# power.net
KiCad netlist of a schematic drawn in Altium Designer
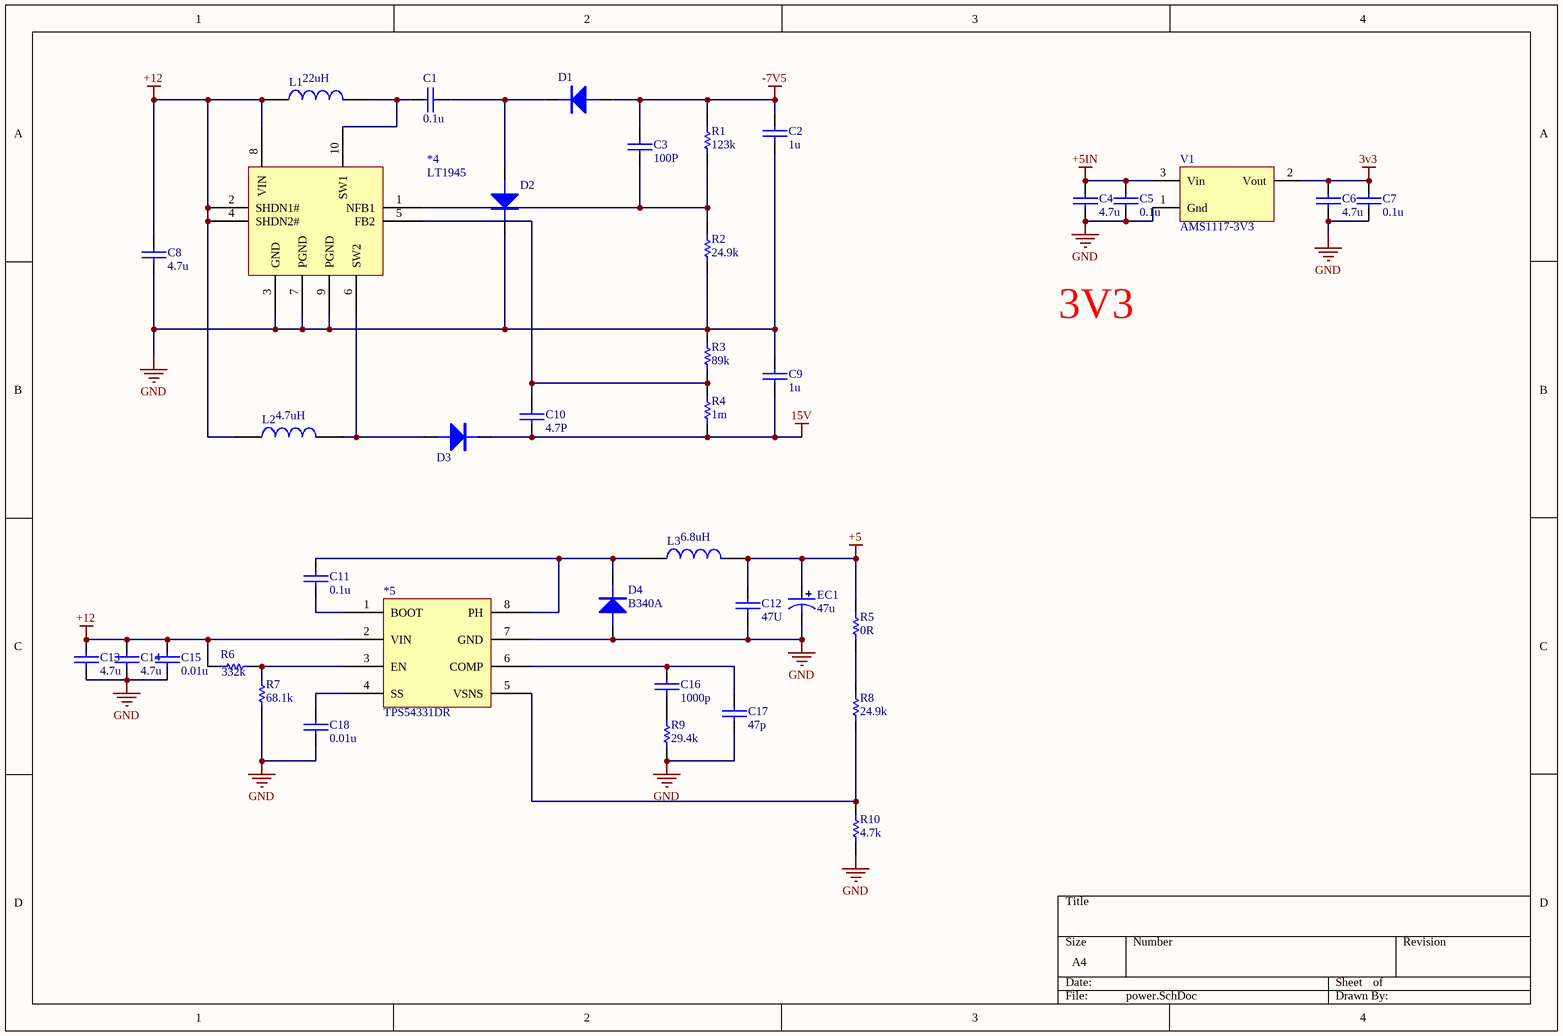
[diagram p0: power.SchDoc]

(export (version "E")
  (design (tool "Eeschema 10.0.6"))
  (components
    (comp (ref "*4")
      (value "LT1945")
      (footprint "LT1945EMS")
      (description "双通道升降压DCDC")
      (libsource (lib "0.03电源") (part "LT1945"))
    )
    (comp (ref "*5")
      (value "TPS54331DR")
      (footprint "SOIC-8")
      (description "降压型DC-DC")
      (libsource (lib "0.03电源") (part "TPS54331DR"))
    )
    (comp (ref "C1")
      (value "0.1u")
      (footprint "0603C")
      (description "无极性电容")
      (libsource (lib "1.00-阻容感") (part "CAP"))
    )
    (comp (ref "C2")
      (value "1u")
      (footprint "0603C")
      (description "无极性电容")
      (libsource (lib "1.00-阻容感") (part "CAP"))
    )
    (comp (ref "C3")
      (value "100P")
      (footprint "0603C")
      (description "无极性电容")
      (libsource (lib "1.00-阻容感") (part "CAP"))
    )
    (comp (ref "C4")
      (value "4.7u")
      (footprint "0603C")
      (description "无极性电容")
      (libsource (lib "1.00-阻容感") (part "CAP"))
    )
    (comp (ref "C5")
      (value "0.1u")
      (footprint "0603C")
      (description "无极性电容")
      (libsource (lib "1.00-阻容感") (part "CAP"))
    )
    (comp (ref "C6")
      (value "4.7u")
      (footprint "0603C")
      (description "无极性电容")
      (libsource (lib "1.00-阻容感") (part "CAP"))
    )
    (comp (ref "C7")
      (value "0.1u")
      (footprint "0603C")
      (description "无极性电容")
      (libsource (lib "1.00-阻容感") (part "CAP"))
    )
    (comp (ref "C8")
      (value "4.7u")
      (footprint "0603C")
      (description "无极性电容")
      (libsource (lib "1.00-阻容感") (part "CAP"))
    )
    (comp (ref "C9")
      (value "1u")
      (footprint "0603C")
      (description "无极性电容")
      (libsource (lib "1.00-阻容感") (part "CAP"))
    )
    (comp (ref "C10")
      (value "4.7P")
      (footprint "0603C")
      (description "无极性电容")
      (libsource (lib "1.00-阻容感") (part "CAP"))
    )
    (comp (ref "C11")
      (value "0.1u")
      (footprint "0603C")
      (description "无极性电容")
      (libsource (lib "1.00-阻容感") (part "CAP"))
    )
    (comp (ref "C12")
      (value "47U")
      (footprint "0603C")
      (description "无极性电容")
      (libsource (lib "1.00-阻容感") (part "CAP"))
    )
    (comp (ref "C13")
      (value "4.7u")
      (footprint "0603C")
      (description "无极性电容")
      (libsource (lib "1.00-阻容感") (part "CAP"))
    )
    (comp (ref "C14")
      (value "4.7u")
      (footprint "0603C")
      (description "无极性电容")
      (libsource (lib "1.00-阻容感") (part "CAP"))
    )
    (comp (ref "C15")
      (value "0.01u")
      (footprint "0603C")
      (description "无极性电容")
      (libsource (lib "1.00-阻容感") (part "CAP"))
    )
    (comp (ref "C16")
      (value "1000p")
      (footprint "0603C")
      (description "无极性电容")
      (libsource (lib "1.00-阻容感") (part "CAP"))
    )
    (comp (ref "C17")
      (value "47p")
      (footprint "0603C")
      (description "无极性电容")
      (libsource (lib "1.00-阻容感") (part "CAP"))
    )
    (comp (ref "C18")
      (value "0.01u")
      (footprint "0603C")
      (description "无极性电容")
      (libsource (lib "1.00-阻容感") (part "CAP"))
    )
    (comp (ref "D1")
      (value "B340A")
      (footprint "SMA/DO-214AC")
      (description "普通二极管")
      (libsource (lib "2.00-二极管") (part "DIODE"))
    )
    (comp (ref "D2")
      (value "B340A")
      (footprint "SMA/DO-214AC")
      (description "普通二极管")
      (libsource (lib "2.00-二极管") (part "DIODE"))
    )
    (comp (ref "D3")
      (value "B340A")
      (footprint "SMA/DO-214AC")
      (description "普通二极管")
      (libsource (lib "2.00-二极管") (part "DIODE"))
    )
    (comp (ref "D4")
      (value "B340A")
      (footprint "SMA/DO-214AC")
      (description "普通二极管")
      (libsource (lib "2.00-二极管") (part "DIODE"))
    )
    (comp (ref "EC1")
      (value "47u")
      (footprint "SMD-EC6.3X6.3X10")
      (description "贴片电解电容")
      (libsource (lib "1.00-阻容感") (part "ECAP"))
    )
    (comp (ref "L1")
      (value "22uH")
      (footprint "L-SMD-0630")
      (description "INDUCTOR")
      (libsource (lib "1.00-阻容感") (part "L"))
    )
    (comp (ref "L2")
      (value "4.7uH")
      (footprint "L-SMD-0630")
      (description "INDUCTOR")
      (libsource (lib "1.00-阻容感") (part "L"))
    )
    (comp (ref "L3")
      (value "6.8uH")
      (footprint "L-SMD-0630")
      (description "INDUCTOR")
      (libsource (lib "1.00-阻容感") (part "L"))
    )
    (comp (ref "R1")
      (value "123k")
      (footprint "0603R")
      (description "电阻")
      (libsource (lib "1.00-阻容感") (part "RES"))
    )
    (comp (ref "R2")
      (value "24.9k")
      (footprint "0603R")
      (description "电阻")
      (libsource (lib "1.00-阻容感") (part "RES"))
    )
    (comp (ref "R3")
      (value "89k")
      (footprint "0603R")
      (description "电阻")
      (libsource (lib "1.00-阻容感") (part "RES"))
    )
    (comp (ref "R4")
      (value "1m")
      (footprint "0603R")
      (description "电阻")
      (libsource (lib "1.00-阻容感") (part "RES"))
    )
    (comp (ref "R5")
      (value "0R")
      (footprint "0603R")
      (description "电阻")
      (libsource (lib "1.00-阻容感") (part "RES"))
    )
    (comp (ref "R6")
      (value "332k")
      (footprint "0603R")
      (description "电阻")
      (libsource (lib "1.00-阻容感") (part "RES"))
    )
    (comp (ref "R7")
      (value "68.1k")
      (footprint "0603R")
      (description "电阻")
      (libsource (lib "1.00-阻容感") (part "RES"))
    )
    (comp (ref "R8")
      (value "24.9k")
      (footprint "0603R")
      (description "电阻")
      (libsource (lib "1.00-阻容感") (part "RES"))
    )
    (comp (ref "R9")
      (value "29.4k")
      (footprint "0603R")
      (description "电阻")
      (libsource (lib "1.00-阻容感") (part "RES"))
    )
    (comp (ref "R10")
      (value "4.7k")
      (footprint "0603R")
      (description "电阻")
      (libsource (lib "1.00-阻容感") (part "RES"))
    )
    (comp (ref "V1")
      (value "AMS1117-3V3")
      (footprint "SOT223_L")
      (description "LDO")
      (libsource (lib "0.03电源") (part "AMS1117"))
    )
  )
  (nets
    (net (code "1") (name "+5") (class "Default")
      (node (ref "C12") (pin "2") (pinfunction "2_2") (pintype "passive"))
      (node (ref "EC1") (pin "1") (pinfunction "1_1") (pintype "passive"))
      (node (ref "L3") (pin "2") (pinfunction "2_2") (pintype "passive"))
      (node (ref "R5") (pin "2") (pinfunction "2_2") (pintype "passive"))
    )
    (net (code "2") (name "+5IN") (class "Default")
      (node (ref "C4") (pin "2") (pinfunction "2_2") (pintype "passive"))
      (node (ref "C5") (pin "2") (pinfunction "2_2") (pintype "passive"))
      (node (ref "V1") (pin "3") (pinfunction "Vin_3") (pintype "passive"))
    )
    (net (code "3") (name "+12") (class "Default")
      (node (ref "*4") (pin "2") (pinfunction "SHDN1#_2") (pintype "passive"))
      (node (ref "*4") (pin "4") (pinfunction "SHDN2#_4") (pintype "passive"))
      (node (ref "*4") (pin "8") (pinfunction "VIN_8") (pintype "passive"))
      (node (ref "*5") (pin "2") (pinfunction "VIN_2") (pintype "passive"))
      (node (ref "C13") (pin "2") (pinfunction "2_2") (pintype "passive"))
      (node (ref "C14") (pin "2") (pinfunction "2_2") (pintype "passive"))
      (node (ref "C15") (pin "2") (pinfunction "2_2") (pintype "passive"))
      (node (ref "C8") (pin "1") (pinfunction "1_1") (pintype "passive"))
      (node (ref "L1") (pin "1") (pinfunction "1_1") (pintype "passive"))
      (node (ref "L2") (pin "1") (pinfunction "1_1") (pintype "passive"))
      (node (ref "R6") (pin "2") (pinfunction "2_2") (pintype "passive"))
    )
    (net (code "4") (name "-7V5") (class "Default")
      (node (ref "C2") (pin "1") (pinfunction "1_1") (pintype "passive"))
      (node (ref "C3") (pin "1") (pinfunction "1_1") (pintype "passive"))
      (node (ref "D1") (pin "A") (pinfunction "A_A") (pintype "passive"))
      (node (ref "R1") (pin "2") (pinfunction "2_2") (pintype "passive"))
    )
    (net (code "5") (name "3v3") (class "Default")
      (node (ref "C6") (pin "2") (pinfunction "2_2") (pintype "passive"))
      (node (ref "C7") (pin "2") (pinfunction "2_2") (pintype "passive"))
      (node (ref "V1") (pin "2") (pinfunction "Vout_2") (pintype "passive"))
    )
    (net (code "6") (name "15V") (class "Default")
      (node (ref "C10") (pin "2") (pinfunction "2_2") (pintype "passive"))
      (node (ref "C9") (pin "2") (pinfunction "2_2") (pintype "passive"))
      (node (ref "D3") (pin "K") (pinfunction "K_K") (pintype "passive"))
      (node (ref "R4") (pin "2") (pinfunction "2_2") (pintype "passive"))
    )
    (net (code "7") (name "GND") (class "Default")
      (node (ref "*4") (pin "3") (pinfunction "GND_3") (pintype "passive"))
      (node (ref "*4") (pin "7") (pinfunction "PGND_7") (pintype "passive"))
      (node (ref "*4") (pin "9") (pinfunction "PGND_9") (pintype "passive"))
      (node (ref "*5") (pin "7") (pinfunction "GND_7") (pintype "passive"))
      (node (ref "C12") (pin "1") (pinfunction "1_1") (pintype "passive"))
      (node (ref "C13") (pin "1") (pinfunction "1_1") (pintype "passive"))
      (node (ref "C14") (pin "1") (pinfunction "1_1") (pintype "passive"))
      (node (ref "C15") (pin "1") (pinfunction "1_1") (pintype "passive"))
      (node (ref "C17") (pin "1") (pinfunction "1_1") (pintype "passive"))
      (node (ref "C18") (pin "1") (pinfunction "1_1") (pintype "passive"))
      (node (ref "C2") (pin "2") (pinfunction "2_2") (pintype "passive"))
      (node (ref "C4") (pin "1") (pinfunction "1_1") (pintype "passive"))
      (node (ref "C5") (pin "1") (pinfunction "1_1") (pintype "passive"))
      (node (ref "C6") (pin "1") (pinfunction "1_1") (pintype "passive"))
      (node (ref "C7") (pin "1") (pinfunction "1_1") (pintype "passive"))
      (node (ref "C8") (pin "2") (pinfunction "2_2") (pintype "passive"))
      (node (ref "C9") (pin "1") (pinfunction "1_1") (pintype "passive"))
      (node (ref "D2") (pin "K") (pinfunction "K_K") (pintype "passive"))
      (node (ref "D4") (pin "A") (pinfunction "A_A") (pintype "passive"))
      (node (ref "EC1") (pin "2") (pinfunction "2_2") (pintype "passive"))
      (node (ref "R10") (pin "1") (pinfunction "1_1") (pintype "passive"))
      (node (ref "R2") (pin "1") (pinfunction "1_1") (pintype "passive"))
      (node (ref "R3") (pin "2") (pinfunction "2_2") (pintype "passive"))
      (node (ref "R7") (pin "1") (pinfunction "1_1") (pintype "passive"))
      (node (ref "R9") (pin "1") (pinfunction "1_1") (pintype "passive"))
      (node (ref "V1") (pin "1") (pinfunction "Gnd_1") (pintype "passive"))
    )
    (net (code "8") (name "Net-(*4-FB2)") (class "Default")
      (node (ref "*4") (pin "5") (pinfunction "FB2_5") (pintype "passive"))
      (node (ref "C10") (pin "1") (pinfunction "1_1") (pintype "passive"))
      (node (ref "R3") (pin "1") (pinfunction "1_1") (pintype "passive"))
      (node (ref "R4") (pin "1") (pinfunction "1_1") (pintype "passive"))
    )
    (net (code "9") (name "Net-(*4-NFB1)") (class "Default")
      (node (ref "*4") (pin "1") (pinfunction "NFB1_1") (pintype "passive"))
      (node (ref "C3") (pin "2") (pinfunction "2_2") (pintype "passive"))
      (node (ref "R1") (pin "1") (pinfunction "1_1") (pintype "passive"))
      (node (ref "R2") (pin "2") (pinfunction "2_2") (pintype "passive"))
    )
    (net (code "10") (name "Net-(*4-SW1)") (class "Default")
      (node (ref "*4") (pin "10") (pinfunction "SW1_10") (pintype "passive"))
      (node (ref "C1") (pin "1") (pinfunction "1_1") (pintype "passive"))
      (node (ref "L1") (pin "2") (pinfunction "2_2") (pintype "passive"))
    )
    (net (code "11") (name "Net-(*4-SW2)") (class "Default")
      (node (ref "*4") (pin "6") (pinfunction "SW2_6") (pintype "passive"))
      (node (ref "D3") (pin "A") (pinfunction "A_A") (pintype "passive"))
      (node (ref "L2") (pin "2") (pinfunction "2_2") (pintype "passive"))
    )
    (net (code "12") (name "Net-(*5-BOOT)") (class "Default")
      (node (ref "*5") (pin "1") (pinfunction "BOOT_1") (pintype "passive"))
      (node (ref "C11") (pin "1") (pinfunction "1_1") (pintype "passive"))
    )
    (net (code "13") (name "Net-(*5-COMP)") (class "Default")
      (node (ref "*5") (pin "6") (pinfunction "COMP_6") (pintype "passive"))
      (node (ref "C16") (pin "2") (pinfunction "2_2") (pintype "passive"))
      (node (ref "C17") (pin "2") (pinfunction "2_2") (pintype "passive"))
    )
    (net (code "14") (name "Net-(*5-EN)") (class "Default")
      (node (ref "*5") (pin "3") (pinfunction "EN_3") (pintype "passive"))
      (node (ref "R6") (pin "1") (pinfunction "1_1") (pintype "passive"))
      (node (ref "R7") (pin "2") (pinfunction "2_2") (pintype "passive"))
    )
    (net (code "15") (name "Net-(*5-PH)") (class "Default")
      (node (ref "*5") (pin "8") (pinfunction "PH_8") (pintype "passive"))
      (node (ref "C11") (pin "2") (pinfunction "2_2") (pintype "passive"))
      (node (ref "D4") (pin "K") (pinfunction "K_K") (pintype "passive"))
      (node (ref "L3") (pin "1") (pinfunction "1_1") (pintype "passive"))
    )
    (net (code "16") (name "Net-(*5-SS)") (class "Default")
      (node (ref "*5") (pin "4") (pinfunction "SS_4") (pintype "passive"))
      (node (ref "C18") (pin "2") (pinfunction "2_2") (pintype "passive"))
    )
    (net (code "17") (name "Net-(*5-VSNS)") (class "Default")
      (node (ref "*5") (pin "5") (pinfunction "VSNS_5") (pintype "passive"))
      (node (ref "R10") (pin "2") (pinfunction "2_2") (pintype "passive"))
      (node (ref "R8") (pin "1") (pinfunction "1_1") (pintype "passive"))
    )
    (net (code "18") (name "Net-(C1-Pad2)") (class "Default")
      (node (ref "C1") (pin "2") (pinfunction "2_2") (pintype "passive"))
      (node (ref "D1") (pin "K") (pinfunction "K_K") (pintype "passive"))
      (node (ref "D2") (pin "A") (pinfunction "A_A") (pintype "passive"))
    )
    (net (code "19") (name "Net-(C16-Pad1)") (class "Default")
      (node (ref "C16") (pin "1") (pinfunction "1_1") (pintype "passive"))
      (node (ref "R9") (pin "2") (pinfunction "2_2") (pintype "passive"))
    )
    (net (code "20") (name "Net-(R5-Pad1)") (class "Default")
      (node (ref "R5") (pin "1") (pinfunction "1_1") (pintype "passive"))
      (node (ref "R8") (pin "2") (pinfunction "2_2") (pintype "passive"))
    )
  )
)
